# SWC_P01.net
KiCad netlist of a schematic drawn in Altium Designer
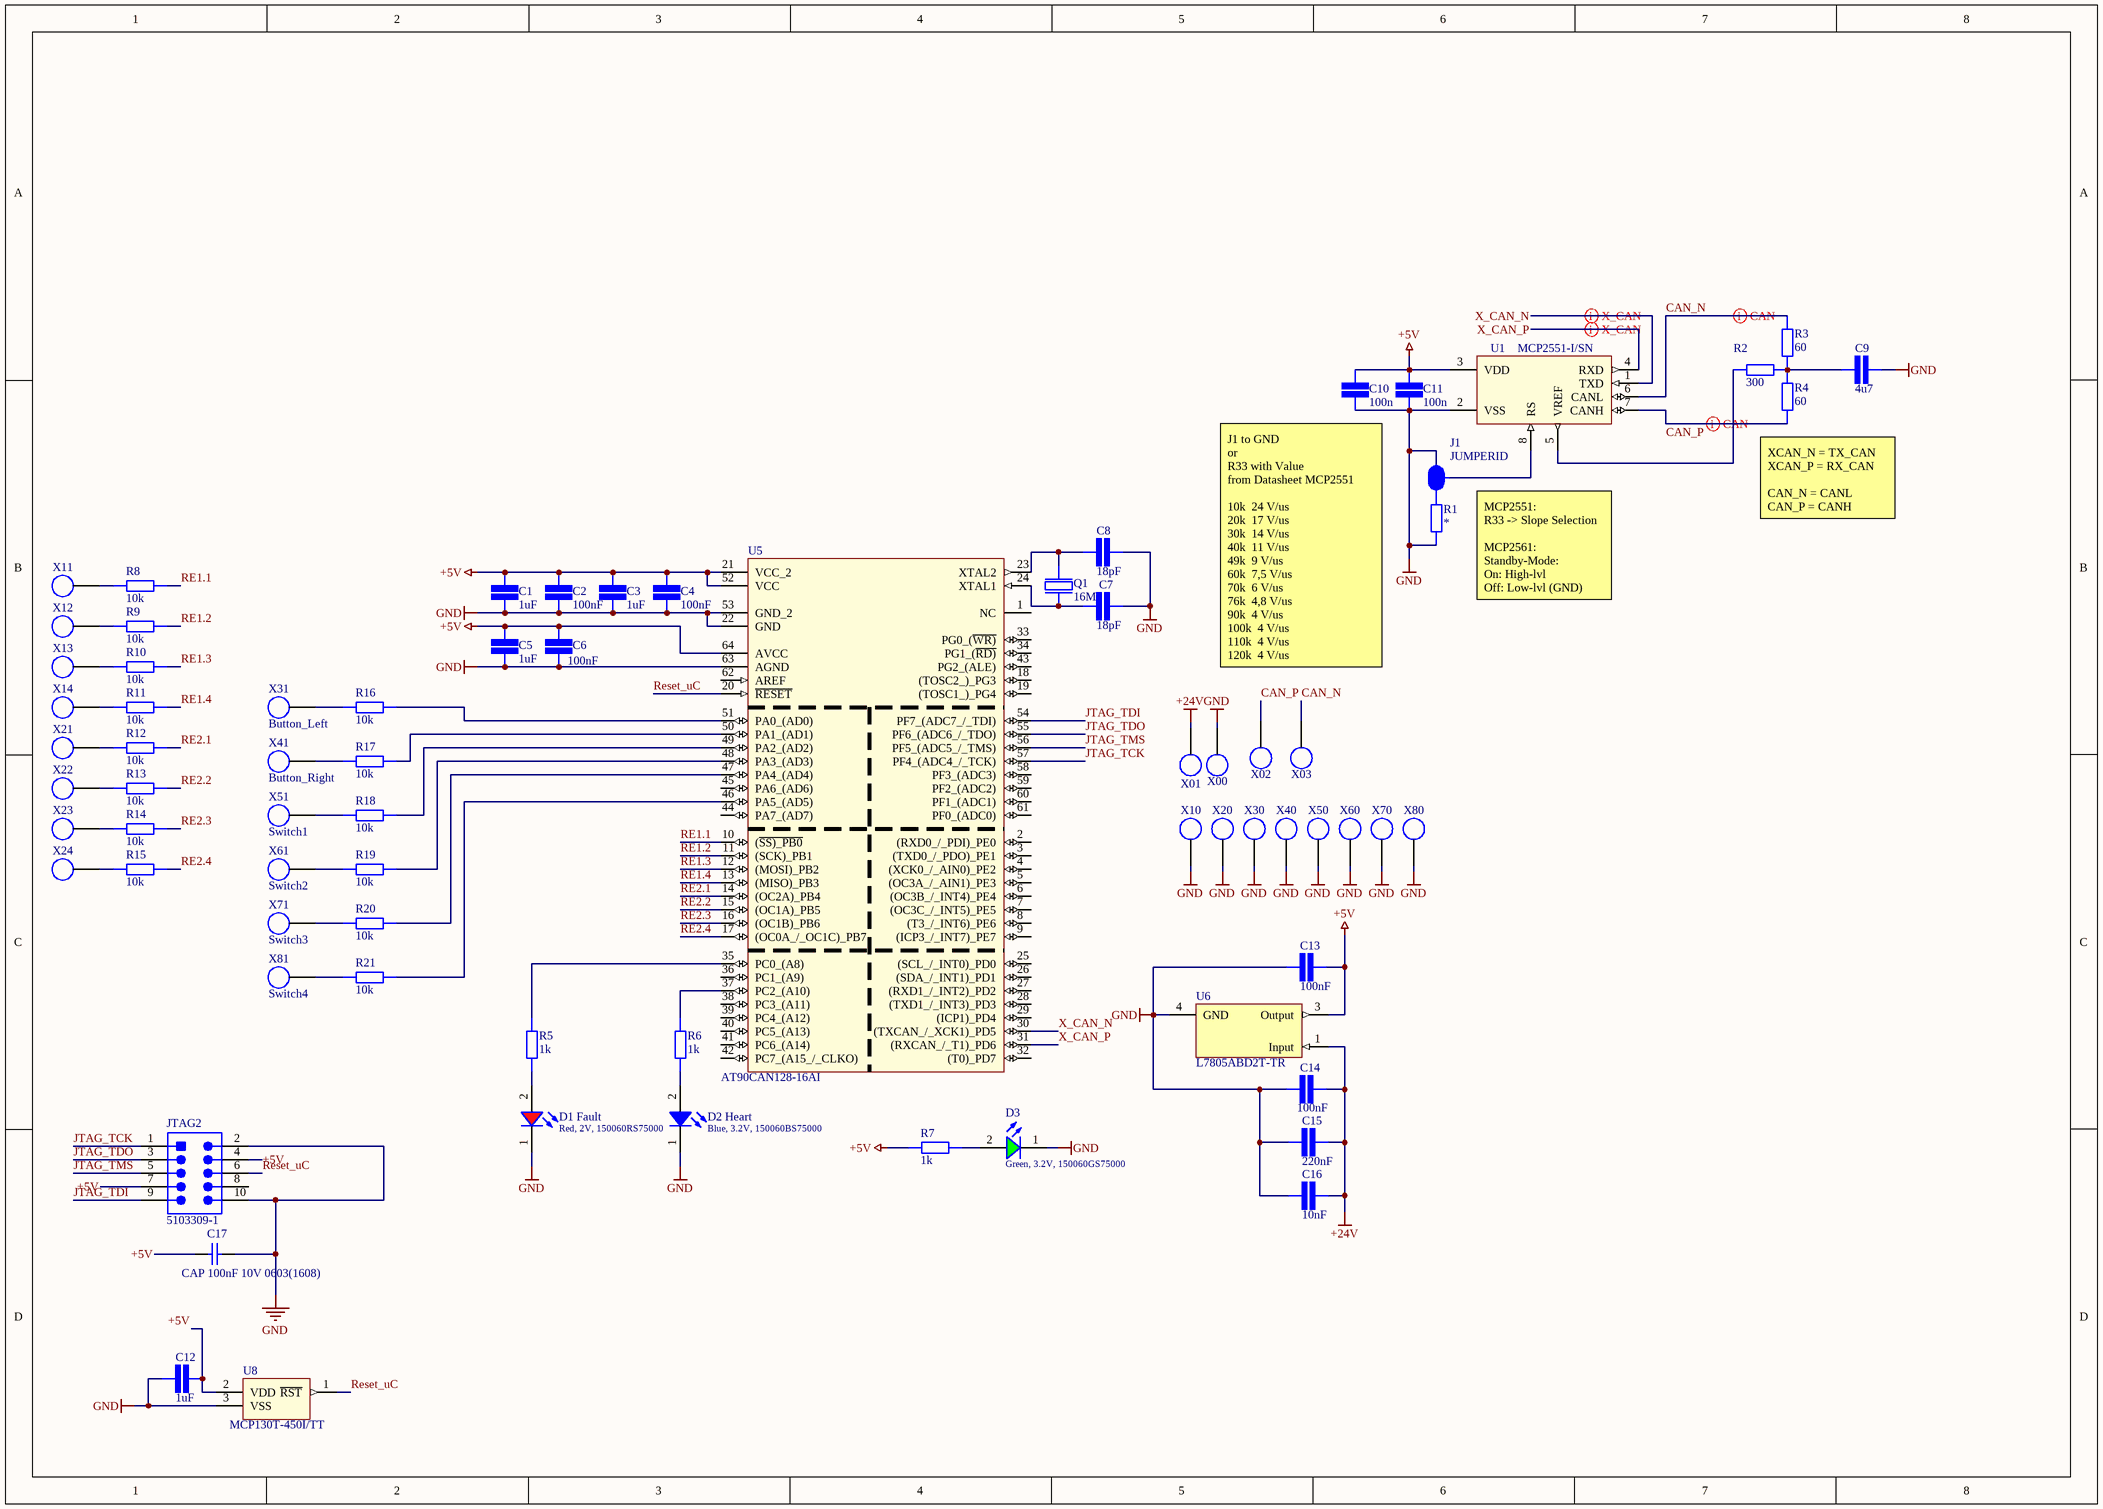
[diagram p0: SWC_P01.SchDoc]

(export (version "E")
  (design (tool "Eeschema 10.0.6"))
  (components
    (comp (ref "C1")
      (value "1uF")
      (footprint "CAP 0603/1608")
      (description "Capacitor with multiple Footprints")
      (fields (field (name "Comment") "SMD Capacitor"))
      (libsource (lib "") (part "SMD Capacitor_1"))
    )
    (comp (ref "C2")
      (value "100nF")
      (footprint "CAP 0603/1608")
      (description "Capacitor with multiple Footprints")
      (fields (field (name "Comment") "SMD Capacitor"))
      (libsource (lib "") (part "SMD Capacitor_1"))
    )
    (comp (ref "C3")
      (value "1uF")
      (footprint "CAP 0603/1608")
      (description "Capacitor with multiple Footprints")
      (fields (field (name "Comment") "SMD Capacitor"))
      (libsource (lib "") (part "SMD Capacitor_1"))
    )
    (comp (ref "C4")
      (value "100nF")
      (footprint "CAP 0603/1608")
      (description "Capacitor with multiple Footprints")
      (fields (field (name "Comment") "SMD Capacitor"))
      (libsource (lib "") (part "SMD Capacitor_1"))
    )
    (comp (ref "C5")
      (value "1uF")
      (footprint "CAP 0603/1608")
      (description "Capacitor with multiple Footprints")
      (fields (field (name "Comment") "SMD Capacitor"))
      (libsource (lib "") (part "SMD Capacitor_1"))
    )
    (comp (ref "C6")
      (value "100nF")
      (footprint "CAP 0603/1608")
      (description "Capacitor with multiple Footprints")
      (fields (field (name "Comment") "SMD Capacitor"))
      (libsource (lib "") (part "SMD Capacitor_1"))
    )
    (comp (ref "C7")
      (value "18pF")
      (footprint "CAP 0603/1608")
      (description "Capacitor with multiple Footprints")
      (fields (field (name "Comment") "SMD Capacitor"))
      (libsource (lib "Standardbauteile") (part "SMD Capacitor"))
    )
    (comp (ref "C8")
      (value "18pF")
      (footprint "CAP 0603/1608")
      (description "Capacitor with multiple Footprints")
      (fields (field (name "Comment") "SMD Capacitor"))
      (libsource (lib "Standardbauteile") (part "SMD Capacitor"))
    )
    (comp (ref "C9")
      (value "4u7")
      (footprint "CAP 0603/1608")
      (description "Capacitor with multiple Footprints")
      (fields (field (name "Comment") "SMD Capacitor"))
      (libsource (lib "") (part "SMD Capacitor_2"))
    )
    (comp (ref "C10")
      (value "100n")
      (footprint "CAP 0603/1608")
      (description "Capacitor with multiple Footprints")
      (fields (field (name "Comment") "SMD Capacitor"))
      (libsource (lib "") (part "SMD Capacitor_1"))
    )
    (comp (ref "C11")
      (value "100n")
      (footprint "CAP 0603/1608")
      (description "Capacitor with multiple Footprints")
      (fields (field (name "Comment") "SMD Capacitor"))
      (libsource (lib "") (part "SMD Capacitor_1"))
    )
    (comp (ref "C12")
      (value "1uF")
      (footprint "CAP 0603/1608")
      (description "Capacitor with multiple Footprints")
      (fields (field (name "Comment") "SMD Capacitor"))
      (libsource (lib "Standardbauteile") (part "SMD Capacitor"))
    )
    (comp (ref "C13")
      (value "100nF")
      (footprint "CAP 0603/1608")
      (description "Capacitor with multiple Footprints")
      (fields (field (name "Comment") "SMD Capacitor"))
      (libsource (lib "Standardbauteile") (part "SMD Capacitor"))
    )
    (comp (ref "C14")
      (value "100nF")
      (footprint "CAP 0603/1608")
      (description "Capacitor with multiple Footprints")
      (fields (field (name "Comment") "SMD Capacitor"))
      (libsource (lib "Standardbauteile") (part "SMD Capacitor"))
    )
    (comp (ref "C15")
      (value "220nF")
      (footprint "CAP 0603/1608")
      (description "Capacitor with multiple Footprints")
      (fields (field (name "Comment") "SMD Capacitor"))
      (libsource (lib "Standardbauteile") (part "SMD Capacitor"))
    )
    (comp (ref "C16")
      (value "10nF")
      (footprint "CAP 0603/1608")
      (description "Capacitor with multiple Footprints")
      (fields (field (name "Comment") "SMD Capacitor"))
      (libsource (lib "Standardbauteile") (part "SMD Capacitor"))
    )
    (comp (ref "C17")
      (value "CAP 100nF 10V 0603(1608)")
      (footprint "CAPC0603(1608)100_L")
      (description "CAP 100nF 10V ±5% 0603 (1608 Metric) Thickness 1mm SMD")
      (fields (field (name "TOLERANCE") "Â±5%"))
      (libsource (lib "Altium Content Vault") (part "CAP"))
    )
    (comp (ref "D1 Fault")
      (value "Red, 2V, 150060RS75000")
      (footprint "WL-SMCW_0603_H=0.7mm")
      (description "WL-SMCW SMT Mono-color Chip LED Waterclear, size 0603, Red, 2V, 140deg")
      (fields (field (name "PART NUMBER") "150060RS75000") (field (name "PUBLISHER") "Wurth Elektronik"))
      (libsource (lib "Altium_WL-SMCW (rev20a)") (part "150060RS75000"))
    )
    (comp (ref "D2 Heart")
      (value "Blue, 3.2V, 150060BS75000")
      (footprint "WL-SMCW_0603_H=0.7mm")
      (description "WL-SMCW SMT Mono-color Chip LED Waterclear, size 0603, Blue, 3.2V, 140deg")
      (fields (field (name "PART NUMBER") "150060BS75000") (field (name "PUBLISHER") "Wurth Elektronik"))
      (libsource (lib "Altium_WL-SMCW (rev20a)") (part "150060BS75000"))
    )
    (comp (ref "D3")
      (value "Green, 3.2V, 150060GS75000")
      (footprint "WL-SMCW_0603_H=0.7mm")
      (description "WL-SMCW SMT Mono-color Chip LED Waterclear, size 0603, Green, 3.2V, 140deg")
      (fields (field (name "PART NUMBER") "150060GS75000") (field (name "PUBLISHER") "Wurth Elektronik"))
      (libsource (lib "Altium_WL-SMCW (rev20a)") (part "150060GS75000"))
    )
    (comp (ref "J1")
      (value "JUMPERID")
      (footprint "SMD-JUMPER-3")
      (libsource (lib "Standardbauteile") (part "SMD Jumper 3"))
    )
    (comp (ref "JTAG2")
      (value "5103309-1")
      (footprint "TECO-5103309-1_V")
      (fields (field (name "MANUFACTURER") "TE Connectivity"))
      (libsource (lib "Altium Content Vault") (part "CN-2P-M-R10"))
    )
    (comp (ref "Q1")
      (value "16M")
      (footprint "NDK NX5032GA")
      (description "16 MHz Quartz")
      (libsource (lib "Standardbauteile") (part "16 MHz Quartz"))
    )
    (comp (ref "R1")
      (value "SMD Resistor")
      (footprint "STACKPOLE CSR0603")
      (description "Resistor with multiple footprints")
      (fields (field (name "ALTIUM_VALUE") "*"))
      (libsource (lib "Standardbauteile") (part "SMD Resistor"))
    )
    (comp (ref "R2")
      (value "300")
      (footprint "STACKPOLE CSR0603")
      (description "Resistor with multiple footprints")
      (fields (field (name "Comment") "SMD Resistor"))
      (libsource (lib "Standardbauteile") (part "SMD Resistor"))
    )
    (comp (ref "R3")
      (value "60")
      (footprint "STACKPOLE CSR0603")
      (description "Resistor with multiple footprints")
      (fields (field (name "Comment") "SMD Resistor"))
      (libsource (lib "Standardbauteile") (part "SMD Resistor"))
    )
    (comp (ref "R4")
      (value "60")
      (footprint "STACKPOLE CSR0603")
      (description "Resistor with multiple footprints")
      (fields (field (name "Comment") "SMD Resistor"))
      (libsource (lib "Standardbauteile") (part "SMD Resistor"))
    )
    (comp (ref "R5")
      (value "1k")
      (footprint "STACKPOLE CSR0603")
      (description "Resistor with multiple footprints")
      (fields (field (name "Comment") "SMD Resistor"))
      (libsource (lib "Standardbauteile") (part "SMD Resistor"))
    )
    (comp (ref "R6")
      (value "1k")
      (footprint "STACKPOLE CSR0603")
      (description "Resistor with multiple footprints")
      (fields (field (name "Comment") "SMD Resistor"))
      (libsource (lib "Standardbauteile") (part "SMD Resistor"))
    )
    (comp (ref "R7")
      (value "1k")
      (footprint "STACKPOLE CSR0603")
      (description "Resistor with multiple footprints")
      (fields (field (name "Comment") "SMD Resistor"))
      (libsource (lib "Standardbauteile") (part "SMD Resistor"))
    )
    (comp (ref "R8")
      (value "10k")
      (footprint "STACKPOLE CSR0603")
      (description "Resistor with multiple footprints")
      (fields (field (name "Comment") "SMD Resistor"))
      (libsource (lib "Standardbauteile") (part "SMD Resistor"))
    )
    (comp (ref "R9")
      (value "10k")
      (footprint "STACKPOLE CSR0603")
      (description "Resistor with multiple footprints")
      (fields (field (name "Comment") "SMD Resistor"))
      (libsource (lib "Standardbauteile") (part "SMD Resistor"))
    )
    (comp (ref "R10")
      (value "10k")
      (footprint "STACKPOLE CSR0603")
      (description "Resistor with multiple footprints")
      (fields (field (name "Comment") "SMD Resistor"))
      (libsource (lib "Standardbauteile") (part "SMD Resistor"))
    )
    (comp (ref "R11")
      (value "10k")
      (footprint "STACKPOLE CSR0603")
      (description "Resistor with multiple footprints")
      (fields (field (name "Comment") "SMD Resistor"))
      (libsource (lib "Standardbauteile") (part "SMD Resistor"))
    )
    (comp (ref "R12")
      (value "10k")
      (footprint "STACKPOLE CSR0603")
      (description "Resistor with multiple footprints")
      (fields (field (name "Comment") "SMD Resistor"))
      (libsource (lib "Standardbauteile") (part "SMD Resistor"))
    )
    (comp (ref "R13")
      (value "10k")
      (footprint "STACKPOLE CSR0603")
      (description "Resistor with multiple footprints")
      (fields (field (name "Comment") "SMD Resistor"))
      (libsource (lib "Standardbauteile") (part "SMD Resistor"))
    )
    (comp (ref "R14")
      (value "10k")
      (footprint "STACKPOLE CSR0603")
      (description "Resistor with multiple footprints")
      (fields (field (name "Comment") "SMD Resistor"))
      (libsource (lib "Standardbauteile") (part "SMD Resistor"))
    )
    (comp (ref "R15")
      (value "10k")
      (footprint "STACKPOLE CSR0603")
      (description "Resistor with multiple footprints")
      (fields (field (name "Comment") "SMD Resistor"))
      (libsource (lib "Standardbauteile") (part "SMD Resistor"))
    )
    (comp (ref "R16")
      (value "10k")
      (footprint "STACKPOLE CSR0603")
      (description "Resistor with multiple footprints")
      (fields (field (name "Comment") "SMD Resistor"))
      (libsource (lib "Standardbauteile") (part "SMD Resistor"))
    )
    (comp (ref "R17")
      (value "10k")
      (footprint "STACKPOLE CSR0603")
      (description "Resistor with multiple footprints")
      (fields (field (name "Comment") "SMD Resistor"))
      (libsource (lib "Standardbauteile") (part "SMD Resistor"))
    )
    (comp (ref "R18")
      (value "10k")
      (footprint "STACKPOLE CSR0603")
      (description "Resistor with multiple footprints")
      (fields (field (name "Comment") "SMD Resistor"))
      (libsource (lib "Standardbauteile") (part "SMD Resistor"))
    )
    (comp (ref "R19")
      (value "10k")
      (footprint "STACKPOLE CSR0603")
      (description "Resistor with multiple footprints")
      (fields (field (name "Comment") "SMD Resistor"))
      (libsource (lib "Standardbauteile") (part "SMD Resistor"))
    )
    (comp (ref "R20")
      (value "10k")
      (footprint "STACKPOLE CSR0603")
      (description "Resistor with multiple footprints")
      (fields (field (name "Comment") "SMD Resistor"))
      (libsource (lib "Standardbauteile") (part "SMD Resistor"))
    )
    (comp (ref "R21")
      (value "10k")
      (footprint "STACKPOLE CSR0603")
      (description "Resistor with multiple footprints")
      (fields (field (name "Comment") "SMD Resistor"))
      (libsource (lib "Standardbauteile") (part "SMD Resistor"))
    )
    (comp (ref "U1")
      (value "MCP2551-I/SN")
      (footprint "*SOIC127P600X175-8N")
      (description "MCP2551 Series 5.5 V 1 Mb/s Surface Mount High-Speed CAN Transceiver - SOIC-8")
      (fields (field (name "MF") "Microchip"))
      (libsource (lib "Eric") (part "MCP2551-I/SN"))
    )
    (comp (ref "U5")
      (value "AT90CAN128-16AI")
      (footprint "*QFP80P1600X1600X120-64N")
      (description "Ic Mcu 8bit 128kb Flash 64tqfp")
      (fields (field (name "MF") "Microchip"))
      (libsource (lib "Eric") (part "AT90CAN128-16AI"))
    )
    (comp (ref "U6")
      (value "L7805ABD2T-TR")
      (footprint "DPAK254P1542X460-3M")
      (description "Linear Voltage Regulators 5.0V 1.5A Positive")
      (libsource (lib "LibJulian") (part "L7805ABD2T-TR"))
    )
    (comp (ref "U8")
      (value "MCP130T-450I/TT")
      (footprint "*SOT95P237X112-3N")
      (description "System Supervisors - Power Supply Monitors with Reset Generators Open Drain Low")
      (fields (field (name "MF") "Microchip") (field (name "MP") "MCP120T-450I/TT"))
      (libsource (lib "Eric") (part "MCP130T-450I/TT"))
    )
    (comp (ref "X00")
      (value "SolderTerminal")
      (footprint "SolderTerminal")
      (libsource (lib "LibJulian") (part "SolderTerminal"))
    )
    (comp (ref "X01")
      (value "SolderTerminal")
      (footprint "SolderTerminal")
      (libsource (lib "LibJulian") (part "SolderTerminal"))
    )
    (comp (ref "X02")
      (value "SolderTerminal")
      (footprint "SolderTerminal")
      (libsource (lib "LibJulian") (part "SolderTerminal"))
    )
    (comp (ref "X03")
      (value "SolderTerminal")
      (footprint "SolderTerminal")
      (libsource (lib "LibJulian") (part "SolderTerminal"))
    )
    (comp (ref "X10")
      (value "SolderTerminal")
      (footprint "SolderTerminal")
      (libsource (lib "LibJulian") (part "SolderTerminal"))
    )
    (comp (ref "X11")
      (value "SolderTerminal")
      (footprint "SolderTerminal")
      (libsource (lib "LibJulian") (part "SolderTerminal"))
    )
    (comp (ref "X12")
      (value "SolderTerminal")
      (footprint "SolderTerminal")
      (libsource (lib "LibJulian") (part "SolderTerminal"))
    )
    (comp (ref "X13")
      (value "SolderTerminal")
      (footprint "SolderTerminal")
      (libsource (lib "LibJulian") (part "SolderTerminal"))
    )
    (comp (ref "X14")
      (value "SolderTerminal")
      (footprint "SolderTerminal")
      (libsource (lib "LibJulian") (part "SolderTerminal"))
    )
    (comp (ref "X20")
      (value "SolderTerminal")
      (footprint "SolderTerminal")
      (libsource (lib "LibJulian") (part "SolderTerminal"))
    )
    (comp (ref "X21")
      (value "SolderTerminal")
      (footprint "SolderTerminal")
      (libsource (lib "LibJulian") (part "SolderTerminal"))
    )
    (comp (ref "X22")
      (value "SolderTerminal")
      (footprint "SolderTerminal")
      (libsource (lib "LibJulian") (part "SolderTerminal"))
    )
    (comp (ref "X23")
      (value "SolderTerminal")
      (footprint "SolderTerminal")
      (libsource (lib "LibJulian") (part "SolderTerminal"))
    )
    (comp (ref "X24")
      (value "SolderTerminal")
      (footprint "SolderTerminal")
      (libsource (lib "LibJulian") (part "SolderTerminal"))
    )
    (comp (ref "X30")
      (value "SolderTerminal")
      (footprint "SolderTerminal")
      (libsource (lib "LibJulian") (part "SolderTerminal"))
    )
    (comp (ref "X31")
      (value "Button_Left")
      (footprint "SolderTerminal")
      (libsource (lib "LibJulian") (part "SolderTerminal"))
    )
    (comp (ref "X40")
      (value "SolderTerminal")
      (footprint "SolderTerminal")
      (libsource (lib "LibJulian") (part "SolderTerminal"))
    )
    (comp (ref "X41")
      (value "Button_Right")
      (footprint "SolderTerminal")
      (libsource (lib "LibJulian") (part "SolderTerminal"))
    )
    (comp (ref "X50")
      (value "SolderTerminal")
      (footprint "SolderTerminal")
      (libsource (lib "LibJulian") (part "SolderTerminal"))
    )
    (comp (ref "X51")
      (value "Switch1")
      (footprint "SolderTerminal")
      (libsource (lib "LibJulian") (part "SolderTerminal"))
    )
    (comp (ref "X60")
      (value "SolderTerminal")
      (footprint "SolderTerminal")
      (libsource (lib "LibJulian") (part "SolderTerminal"))
    )
    (comp (ref "X61")
      (value "Switch2")
      (footprint "SolderTerminal")
      (libsource (lib "LibJulian") (part "SolderTerminal"))
    )
    (comp (ref "X70")
      (value "SolderTerminal")
      (footprint "SolderTerminal")
      (libsource (lib "LibJulian") (part "SolderTerminal"))
    )
    (comp (ref "X71")
      (value "Switch3")
      (footprint "SolderTerminal")
      (libsource (lib "LibJulian") (part "SolderTerminal"))
    )
    (comp (ref "X80")
      (value "SolderTerminal")
      (footprint "SolderTerminal")
      (libsource (lib "LibJulian") (part "SolderTerminal"))
    )
    (comp (ref "X81")
      (value "Switch4")
      (footprint "SolderTerminal")
      (libsource (lib "LibJulian") (part "SolderTerminal"))
    )
  )
  (nets
    (net (code "1") (name "+5V") (class "Default")
      (node (ref "C1") (pin "2") (pinfunction "2_2") (pintype "passive"))
      (node (ref "C10") (pin "2") (pinfunction "2_2") (pintype "passive"))
      (node (ref "C11") (pin "2") (pinfunction "2_2") (pintype "passive"))
      (node (ref "C12") (pin "1") (pinfunction "1_1") (pintype "passive"))
      (node (ref "C13") (pin "1") (pinfunction "1_1") (pintype "passive"))
      (node (ref "C17") (pin "1") (pinfunction "1_1") (pintype "passive"))
      (node (ref "C2") (pin "2") (pinfunction "2_2") (pintype "passive"))
      (node (ref "C3") (pin "2") (pinfunction "2_2") (pintype "passive"))
      (node (ref "C4") (pin "2") (pinfunction "2_2") (pintype "passive"))
      (node (ref "C5") (pin "2") (pinfunction "2_2") (pintype "passive"))
      (node (ref "C6") (pin "2") (pinfunction "2_2") (pintype "passive"))
      (node (ref "JTAG2") (pin "4") (pinfunction "4_4") (pintype "passive"))
      (node (ref "JTAG2") (pin "7") (pinfunction "7_7") (pintype "passive"))
      (node (ref "R7") (pin "2") (pinfunction "2_2") (pintype "passive"))
      (node (ref "U1") (pin "3") (pinfunction "VDD_3") (pintype "power_in"))
      (node (ref "U5") (pin "21") (pinfunction "VCC_2_21") (pintype "power_in"))
      (node (ref "U5") (pin "52") (pinfunction "VCC_52") (pintype "power_in"))
      (node (ref "U5") (pin "64") (pinfunction "AVCC_64") (pintype "power_in"))
      (node (ref "U6") (pin "3") (pinfunction "Output_3") (pintype "output"))
      (node (ref "U8") (pin "2") (pinfunction "VDD_2") (pintype "power_in"))
    )
    (net (code "2") (name "+24V") (class "Default")
      (node (ref "C14") (pin "1") (pinfunction "1_1") (pintype "passive"))
      (node (ref "C15") (pin "1") (pinfunction "1_1") (pintype "passive"))
      (node (ref "C16") (pin "1") (pinfunction "1_1") (pintype "passive"))
      (node (ref "U6") (pin "1") (pinfunction "Input_1") (pintype "input"))
      (node (ref "X01") (pin "1") (pinfunction "Terminal_1") (pintype "passive"))
    )
    (net (code "3") (name "/CAN_N") (class "Default")
      (node (ref "R3") (pin "1") (pinfunction "1_1") (pintype "passive"))
      (node (ref "U1") (pin "6") (pinfunction "CANL_6") (pintype "bidirectional"))
      (node (ref "X03") (pin "1") (pinfunction "Terminal_1") (pintype "passive"))
    )
    (net (code "4") (name "/CAN_P") (class "Default")
      (node (ref "R4") (pin "2") (pinfunction "2_2") (pintype "passive"))
      (node (ref "U1") (pin "7") (pinfunction "CANH_7") (pintype "bidirectional"))
      (node (ref "X02") (pin "1") (pinfunction "Terminal_1") (pintype "passive"))
    )
    (net (code "5") (name "/JTAG_TCK") (class "Default")
      (node (ref "JTAG2") (pin "1") (pinfunction "1_1") (pintype "passive"))
      (node (ref "U5") (pin "57") (pinfunction "PF4_(ADC4_/_TCK)_57") (pintype "bidirectional"))
    )
    (net (code "6") (name "/JTAG_TDI") (class "Default")
      (node (ref "JTAG2") (pin "9") (pinfunction "9_9") (pintype "passive"))
      (node (ref "U5") (pin "54") (pinfunction "PF7_(ADC7_/_TDI)_54") (pintype "bidirectional"))
    )
    (net (code "7") (name "/JTAG_TDO") (class "Default")
      (node (ref "JTAG2") (pin "3") (pinfunction "3_3") (pintype "passive"))
      (node (ref "U5") (pin "55") (pinfunction "PF6_(ADC6_/_TDO)_55") (pintype "bidirectional"))
    )
    (net (code "8") (name "/JTAG_TMS") (class "Default")
      (node (ref "JTAG2") (pin "5") (pinfunction "5_5") (pintype "passive"))
      (node (ref "U5") (pin "56") (pinfunction "PF5_(ADC5_/_TMS)_56") (pintype "bidirectional"))
    )
    (net (code "9") (name "/RE1.1") (class "Default")
      (node (ref "R8") (pin "1") (pinfunction "1_1") (pintype "passive"))
      (node (ref "U5") (pin "10") (pinfunction "(~{SS)_PB0}_10") (pintype "bidirectional"))
    )
    (net (code "10") (name "/RE1.2") (class "Default")
      (node (ref "R9") (pin "1") (pinfunction "1_1") (pintype "passive"))
      (node (ref "U5") (pin "11") (pinfunction "(SCK)_PB1_11") (pintype "bidirectional"))
    )
    (net (code "11") (name "/RE1.3") (class "Default")
      (node (ref "R10") (pin "1") (pinfunction "1_1") (pintype "passive"))
      (node (ref "U5") (pin "12") (pinfunction "(MOSI)_PB2_12") (pintype "bidirectional"))
    )
    (net (code "12") (name "/RE1.4") (class "Default")
      (node (ref "R11") (pin "1") (pinfunction "1_1") (pintype "passive"))
      (node (ref "U5") (pin "13") (pinfunction "(MISO)_PB3_13") (pintype "bidirectional"))
    )
    (net (code "13") (name "/RE2.1") (class "Default")
      (node (ref "R12") (pin "1") (pinfunction "1_1") (pintype "passive"))
      (node (ref "U5") (pin "14") (pinfunction "(OC2A)_PB4_14") (pintype "bidirectional"))
    )
    (net (code "14") (name "/RE2.2") (class "Default")
      (node (ref "R13") (pin "1") (pinfunction "1_1") (pintype "passive"))
      (node (ref "U5") (pin "15") (pinfunction "(OC1A)_PB5_15") (pintype "bidirectional"))
    )
    (net (code "15") (name "/RE2.3") (class "Default")
      (node (ref "R14") (pin "1") (pinfunction "1_1") (pintype "passive"))
      (node (ref "U5") (pin "16") (pinfunction "(OC1B)_PB6_16") (pintype "bidirectional"))
    )
    (net (code "16") (name "/RE2.4") (class "Default")
      (node (ref "R15") (pin "1") (pinfunction "1_1") (pintype "passive"))
      (node (ref "U5") (pin "17") (pinfunction "(OC0A_/_OC1C)_PB7_17") (pintype "bidirectional"))
    )
    (net (code "17") (name "/Reset_uC") (class "Default")
      (node (ref "JTAG2") (pin "6") (pinfunction "6_6") (pintype "passive"))
      (node (ref "U5") (pin "20") (pinfunction "~{RESET}_20") (pintype "input"))
      (node (ref "U8") (pin "1") (pinfunction "~{RST}_1") (pintype "output"))
    )
    (net (code "18") (name "/X_CAN_N") (class "Default")
      (node (ref "U1") (pin "1") (pinfunction "TXD_1") (pintype "input"))
      (node (ref "U5") (pin "30") (pinfunction "(TXCAN_/_XCK1)_PD5_30") (pintype "bidirectional"))
    )
    (net (code "19") (name "/X_CAN_P") (class "Default")
      (node (ref "U1") (pin "4") (pinfunction "RXD_4") (pintype "output"))
      (node (ref "U5") (pin "31") (pinfunction "(RXCAN_/_T1)_PD6_31") (pintype "bidirectional"))
    )
    (net (code "20") (name "GND") (class "Default")
      (node (ref "C1") (pin "1") (pinfunction "1_1") (pintype "passive"))
      (node (ref "C10") (pin "1") (pinfunction "1_1") (pintype "passive"))
      (node (ref "C11") (pin "1") (pinfunction "1_1") (pintype "passive"))
      (node (ref "C12") (pin "2") (pinfunction "2_2") (pintype "passive"))
      (node (ref "C13") (pin "2") (pinfunction "2_2") (pintype "passive"))
      (node (ref "C14") (pin "2") (pinfunction "2_2") (pintype "passive"))
      (node (ref "C15") (pin "2") (pinfunction "2_2") (pintype "passive"))
      (node (ref "C16") (pin "2") (pinfunction "2_2") (pintype "passive"))
      (node (ref "C17") (pin "2") (pinfunction "2_2") (pintype "passive"))
      (node (ref "C2") (pin "1") (pinfunction "1_1") (pintype "passive"))
      (node (ref "C3") (pin "1") (pinfunction "1_1") (pintype "passive"))
      (node (ref "C4") (pin "1") (pinfunction "1_1") (pintype "passive"))
      (node (ref "C5") (pin "1") (pinfunction "1_1") (pintype "passive"))
      (node (ref "C6") (pin "1") (pinfunction "1_1") (pintype "passive"))
      (node (ref "C7") (pin "1") (pinfunction "1_1") (pintype "passive"))
      (node (ref "C8") (pin "1") (pinfunction "1_1") (pintype "passive"))
      (node (ref "C9") (pin "2") (pinfunction "2_2") (pintype "passive"))
      (node (ref "D1 Fault") (pin "1") (pinfunction "K_1") (pintype "passive"))
      (node (ref "D2 Heart") (pin "1") (pinfunction "K_1") (pintype "passive"))
      (node (ref "D3") (pin "1") (pinfunction "K_1") (pintype "passive"))
      (node (ref "J1") (pin "1") (pinfunction "1_1") (pintype "passive"))
      (node (ref "JTAG2") (pin "10") (pinfunction "10_10") (pintype "passive"))
      (node (ref "JTAG2") (pin "2") (pinfunction "2_2") (pintype "passive"))
      (node (ref "R1") (pin "1") (pinfunction "1_1") (pintype "passive"))
      (node (ref "U1") (pin "2") (pinfunction "VSS_2") (pintype "passive"))
      (node (ref "U5") (pin "22") (pinfunction "GND_22") (pintype "passive"))
      (node (ref "U5") (pin "53") (pinfunction "GND_2_53") (pintype "passive"))
      (node (ref "U5") (pin "63") (pinfunction "AGND_63") (pintype "passive"))
      (node (ref "U6") (pin "4") (pinfunction "GND_4") (pintype "passive"))
      (node (ref "U8") (pin "3") (pinfunction "VSS_3") (pintype "power_in"))
      (node (ref "X00") (pin "1") (pinfunction "Terminal_1") (pintype "passive"))
      (node (ref "X10") (pin "1") (pinfunction "Terminal_1") (pintype "passive"))
      (node (ref "X20") (pin "1") (pinfunction "Terminal_1") (pintype "passive"))
      (node (ref "X30") (pin "1") (pinfunction "Terminal_1") (pintype "passive"))
      (node (ref "X40") (pin "1") (pinfunction "Terminal_1") (pintype "passive"))
      (node (ref "X50") (pin "1") (pinfunction "Terminal_1") (pintype "passive"))
      (node (ref "X60") (pin "1") (pinfunction "Terminal_1") (pintype "passive"))
      (node (ref "X70") (pin "1") (pinfunction "Terminal_1") (pintype "passive"))
      (node (ref "X80") (pin "1") (pinfunction "Terminal_1") (pintype "passive"))
    )
    (net (code "21") (name "Net-(C9-Pad1)") (class "Default")
      (node (ref "C9") (pin "1") (pinfunction "1_1") (pintype "passive"))
      (node (ref "R2") (pin "2") (pinfunction "2_2") (pintype "passive"))
      (node (ref "R3") (pin "2") (pinfunction "2_2") (pintype "passive"))
      (node (ref "R4") (pin "1") (pinfunction "1_1") (pintype "passive"))
    )
    (net (code "22") (name "Net-(D1 Fault-A)") (class "Default")
      (node (ref "D1 Fault") (pin "2") (pinfunction "A_2") (pintype "passive"))
      (node (ref "R5") (pin "2") (pinfunction "2_2") (pintype "passive"))
    )
    (net (code "23") (name "Net-(D2 Heart-A)") (class "Default")
      (node (ref "D2 Heart") (pin "2") (pinfunction "A_2") (pintype "passive"))
      (node (ref "R6") (pin "2") (pinfunction "2_2") (pintype "passive"))
    )
    (net (code "24") (name "Net-(D3-A)") (class "Default")
      (node (ref "D3") (pin "2") (pinfunction "A_2") (pintype "passive"))
      (node (ref "R7") (pin "1") (pinfunction "1_1") (pintype "passive"))
    )
    (net (code "25") (name "Net-(J1-Pad3)") (class "Default")
      (node (ref "J1") (pin "3") (pinfunction "3_3") (pintype "passive"))
      (node (ref "R1") (pin "2") (pinfunction "2_2") (pintype "passive"))
    )
    (net (code "26") (name "Net-(U1-RS)") (class "Default")
      (node (ref "J1") (pin "2") (pinfunction "2_2") (pintype "passive"))
      (node (ref "U1") (pin "8") (pinfunction "RS_8") (pintype "input"))
    )
    (net (code "27") (name "Net-(U1-VREF)") (class "Default")
      (node (ref "R2") (pin "1") (pinfunction "1_1") (pintype "passive"))
      (node (ref "U1") (pin "5") (pinfunction "VREF_5") (pintype "output"))
    )
    (net (code "28") (name "Net-(U5-PA0_(AD0))") (class "Default")
      (node (ref "R16") (pin "2") (pinfunction "2_2") (pintype "passive"))
      (node (ref "U5") (pin "51") (pinfunction "PA0_(AD0)_51") (pintype "bidirectional"))
    )
    (net (code "29") (name "Net-(U5-PA1_(AD1))") (class "Default")
      (node (ref "R17") (pin "2") (pinfunction "2_2") (pintype "passive"))
      (node (ref "U5") (pin "50") (pinfunction "PA1_(AD1)_50") (pintype "bidirectional"))
    )
    (net (code "30") (name "Net-(U5-PA2_(AD2))") (class "Default")
      (node (ref "R18") (pin "2") (pinfunction "2_2") (pintype "passive"))
      (node (ref "U5") (pin "49") (pinfunction "PA2_(AD2)_49") (pintype "bidirectional"))
    )
    (net (code "31") (name "Net-(U5-PA3_(AD3))") (class "Default")
      (node (ref "R19") (pin "2") (pinfunction "2_2") (pintype "passive"))
      (node (ref "U5") (pin "48") (pinfunction "PA3_(AD3)_48") (pintype "bidirectional"))
    )
    (net (code "32") (name "Net-(U5-PA4_(AD4))") (class "Default")
      (node (ref "R20") (pin "2") (pinfunction "2_2") (pintype "passive"))
      (node (ref "U5") (pin "47") (pinfunction "PA4_(AD4)_47") (pintype "bidirectional"))
    )
    (net (code "33") (name "Net-(U5-PA5_(AD5))") (class "Default")
      (node (ref "R21") (pin "2") (pinfunction "2_2") (pintype "passive"))
      (node (ref "U5") (pin "46") (pinfunction "PA5_(AD5)_46") (pintype "bidirectional"))
    )
    (net (code "34") (name "Net-(U5-PC0_(A8))") (class "Default")
      (node (ref "R5") (pin "1") (pinfunction "1_1") (pintype "passive"))
      (node (ref "U5") (pin "35") (pinfunction "PC0_(A8)_35") (pintype "bidirectional"))
    )
    (net (code "35") (name "Net-(U5-PC2_(A10))") (class "Default")
      (node (ref "R6") (pin "1") (pinfunction "1_1") (pintype "passive"))
      (node (ref "U5") (pin "37") (pinfunction "PC2_(A10)_37") (pintype "bidirectional"))
    )
    (net (code "36") (name "Net-(U5-XTAL1)") (class "Default")
      (node (ref "C7") (pin "2") (pinfunction "2_2") (pintype "passive"))
      (node (ref "Q1") (pin "1") (pinfunction "1_1") (pintype "passive"))
      (node (ref "U5") (pin "24") (pinfunction "XTAL1_24") (pintype "input"))
    )
    (net (code "37") (name "Net-(U5-XTAL2)") (class "Default")
      (node (ref "C8") (pin "2") (pinfunction "2_2") (pintype "passive"))
      (node (ref "Q1") (pin "2") (pinfunction "2_2") (pintype "passive"))
      (node (ref "U5") (pin "23") (pinfunction "XTAL2_23") (pintype "output"))
    )
    (net (code "38") (name "Net-(X11-Terminal)") (class "Default")
      (node (ref "R8") (pin "2") (pinfunction "2_2") (pintype "passive"))
      (node (ref "X11") (pin "1") (pinfunction "Terminal_1") (pintype "passive"))
    )
    (net (code "39") (name "Net-(X12-Terminal)") (class "Default")
      (node (ref "R9") (pin "2") (pinfunction "2_2") (pintype "passive"))
      (node (ref "X12") (pin "1") (pinfunction "Terminal_1") (pintype "passive"))
    )
    (net (code "40") (name "Net-(X13-Terminal)") (class "Default")
      (node (ref "R10") (pin "2") (pinfunction "2_2") (pintype "passive"))
      (node (ref "X13") (pin "1") (pinfunction "Terminal_1") (pintype "passive"))
    )
    (net (code "41") (name "Net-(X14-Terminal)") (class "Default")
      (node (ref "R11") (pin "2") (pinfunction "2_2") (pintype "passive"))
      (node (ref "X14") (pin "1") (pinfunction "Terminal_1") (pintype "passive"))
    )
    (net (code "42") (name "Net-(X21-Terminal)") (class "Default")
      (node (ref "R12") (pin "2") (pinfunction "2_2") (pintype "passive"))
      (node (ref "X21") (pin "1") (pinfunction "Terminal_1") (pintype "passive"))
    )
    (net (code "43") (name "Net-(X22-Terminal)") (class "Default")
      (node (ref "R13") (pin "2") (pinfunction "2_2") (pintype "passive"))
      (node (ref "X22") (pin "1") (pinfunction "Terminal_1") (pintype "passive"))
    )
    (net (code "44") (name "Net-(X23-Terminal)") (class "Default")
      (node (ref "R14") (pin "2") (pinfunction "2_2") (pintype "passive"))
      (node (ref "X23") (pin "1") (pinfunction "Terminal_1") (pintype "passive"))
    )
    (net (code "45") (name "Net-(X24-Terminal)") (class "Default")
      (node (ref "R15") (pin "2") (pinfunction "2_2") (pintype "passive"))
      (node (ref "X24") (pin "1") (pinfunction "Terminal_1") (pintype "passive"))
    )
    (net (code "46") (name "Net-(X31-Terminal)") (class "Default")
      (node (ref "R16") (pin "1") (pinfunction "1_1") (pintype "passive"))
      (node (ref "X31") (pin "1") (pinfunction "Terminal_1") (pintype "passive"))
    )
    (net (code "47") (name "Net-(X41-Terminal)") (class "Default")
      (node (ref "R17") (pin "1") (pinfunction "1_1") (pintype "passive"))
      (node (ref "X41") (pin "1") (pinfunction "Terminal_1") (pintype "passive"))
    )
    (net (code "48") (name "Net-(X51-Terminal)") (class "Default")
      (node (ref "R18") (pin "1") (pinfunction "1_1") (pintype "passive"))
      (node (ref "X51") (pin "1") (pinfunction "Terminal_1") (pintype "passive"))
    )
    (net (code "49") (name "Net-(X61-Terminal)") (class "Default")
      (node (ref "R19") (pin "1") (pinfunction "1_1") (pintype "passive"))
      (node (ref "X61") (pin "1") (pinfunction "Terminal_1") (pintype "passive"))
    )
    (net (code "50") (name "Net-(X71-Terminal)") (class "Default")
      (node (ref "R20") (pin "1") (pinfunction "1_1") (pintype "passive"))
      (node (ref "X71") (pin "1") (pinfunction "Terminal_1") (pintype "passive"))
    )
    (net (code "51") (name "Net-(X81-Terminal)") (class "Default")
      (node (ref "R21") (pin "1") (pinfunction "1_1") (pintype "passive"))
      (node (ref "X81") (pin "1") (pinfunction "Terminal_1") (pintype "passive"))
    )
    (net (code "52") (name "unconnected-(JTAG2-Pad8)") (class "Default")
      (node (ref "JTAG2") (pin "8") (pinfunction "8_8") (pintype "passive"))
    )
    (net (code "53") (name "unconnected-(U5-(ICP1)_PD4-Pad29)") (class "Default")
      (node (ref "U5") (pin "29") (pinfunction "(ICP1)_PD4_29") (pintype "bidirectional"))
    )
    (net (code "54") (name "unconnected-(U5-(ICP3_{slash}_INT7)_PE7-Pad9)") (class "Default")
      (node (ref "U5") (pin "9") (pinfunction "(ICP3_/_INT7)_PE7_9") (pintype "bidirectional"))
    )
    (net (code "55") (name "unconnected-(U5-(OC3A_{slash}_AIN1)_PE3-Pad5)") (class "Default")
      (node (ref "U5") (pin "5") (pinfunction "(OC3A_/_AIN1)_PE3_5") (pintype "bidirectional"))
    )
    (net (code "56") (name "unconnected-(U5-(OC3B_{slash}_INT4)_PE4-Pad6)") (class "Default")
      (node (ref "U5") (pin "6") (pinfunction "(OC3B_/_INT4)_PE4_6") (pintype "bidirectional"))
    )
    (net (code "57") (name "unconnected-(U5-(OC3C_{slash}_INT5)_PE5-Pad7)") (class "Default")
      (node (ref "U5") (pin "7") (pinfunction "(OC3C_/_INT5)_PE5_7") (pintype "bidirectional"))
    )
    (net (code "58") (name "unconnected-(U5-(RXD0_{slash}_PDI)_PE0-Pad2)") (class "Default")
      (node (ref "U5") (pin "2") (pinfunction "(RXD0_/_PDI)_PE0_2") (pintype "bidirectional"))
    )
    (net (code "59") (name "unconnected-(U5-(RXD1_{slash}_INT2)_PD2-Pad27)") (class "Default")
      (node (ref "U5") (pin "27") (pinfunction "(RXD1_/_INT2)_PD2_27") (pintype "bidirectional"))
    )
    (net (code "60") (name "unconnected-(U5-(SCL_{slash}_INT0)_PD0-Pad25)") (class "Default")
      (node (ref "U5") (pin "25") (pinfunction "(SCL_/_INT0)_PD0_25") (pintype "bidirectional"))
    )
    (net (code "61") (name "unconnected-(U5-(SDA_{slash}_INT1)_PD1-Pad26)") (class "Default")
      (node (ref "U5") (pin "26") (pinfunction "(SDA_/_INT1)_PD1_26") (pintype "bidirectional"))
    )
    (net (code "62") (name "unconnected-(U5-(T0)_PD7-Pad32)") (class "Default")
      (node (ref "U5") (pin "32") (pinfunction "(T0)_PD7_32") (pintype "bidirectional"))
    )
    (net (code "63") (name "unconnected-(U5-(T3_{slash}_INT6)_PE6-Pad8)") (class "Default")
      (node (ref "U5") (pin "8") (pinfunction "(T3_/_INT6)_PE6_8") (pintype "bidirectional"))
    )
    (net (code "64") (name "unconnected-(U5-(TOSC1_)_PG4-Pad19)") (class "Default")
      (node (ref "U5") (pin "19") (pinfunction "(TOSC1_)_PG4_19") (pintype "bidirectional"))
    )
    (net (code "65") (name "unconnected-(U5-(TOSC2_)_PG3-Pad18)") (class "Default")
      (node (ref "U5") (pin "18") (pinfunction "(TOSC2_)_PG3_18") (pintype "bidirectional"))
    )
    (net (code "66") (name "unconnected-(U5-(TXD0_{slash}_PDO)_PE1-Pad3)") (class "Default")
      (node (ref "U5") (pin "3") (pinfunction "(TXD0_/_PDO)_PE1_3") (pintype "bidirectional"))
    )
    (net (code "67") (name "unconnected-(U5-(TXD1_{slash}_INT3)_PD3-Pad28)") (class "Default")
      (node (ref "U5") (pin "28") (pinfunction "(TXD1_/_INT3)_PD3_28") (pintype "bidirectional"))
    )
    (net (code "68") (name "unconnected-(U5-(XCK0_{slash}_AIN0)_PE2-Pad4)") (class "Default")
      (node (ref "U5") (pin "4") (pinfunction "(XCK0_/_AIN0)_PE2_4") (pintype "bidirectional"))
    )
    (net (code "69") (name "unconnected-(U5-AREF-Pad62)") (class "Default")
      (node (ref "U5") (pin "62") (pinfunction "AREF_62") (pintype "input"))
    )
    (net (code "70") (name "unconnected-(U5-NC-Pad1)") (class "Default")
      (node (ref "U5") (pin "1") (pinfunction "NC_1") (pintype "passive"))
    )
    (net (code "71") (name "unconnected-(U5-PA6_(AD6)-Pad45)") (class "Default")
      (node (ref "U5") (pin "45") (pinfunction "PA6_(AD6)_45") (pintype "bidirectional"))
    )
    (net (code "72") (name "unconnected-(U5-PA7_(AD7)-Pad44)") (class "Default")
      (node (ref "U5") (pin "44") (pinfunction "PA7_(AD7)_44") (pintype "bidirectional"))
    )
    (net (code "73") (name "unconnected-(U5-PC1_(A9)-Pad36)") (class "Default")
      (node (ref "U5") (pin "36") (pinfunction "PC1_(A9)_36") (pintype "bidirectional"))
    )
    (net (code "74") (name "unconnected-(U5-PC3_(A11)-Pad38)") (class "Default")
      (node (ref "U5") (pin "38") (pinfunction "PC3_(A11)_38") (pintype "bidirectional"))
    )
    (net (code "75") (name "unconnected-(U5-PC4_(A12)-Pad39)") (class "Default")
      (node (ref "U5") (pin "39") (pinfunction "PC4_(A12)_39") (pintype "bidirectional"))
    )
    (net (code "76") (name "unconnected-(U5-PC5_(A13)-Pad40)") (class "Default")
      (node (ref "U5") (pin "40") (pinfunction "PC5_(A13)_40") (pintype "bidirectional"))
    )
    (net (code "77") (name "unconnected-(U5-PC6_(A14)-Pad41)") (class "Default")
      (node (ref "U5") (pin "41") (pinfunction "PC6_(A14)_41") (pintype "bidirectional"))
    )
    (net (code "78") (name "unconnected-(U5-PC7_(A15_{slash}_CLKO)-Pad42)") (class "Default")
      (node (ref "U5") (pin "42") (pinfunction "PC7_(A15_/_CLKO)_42") (pintype "bidirectional"))
    )
    (net (code "79") (name "unconnected-(U5-PF0_(ADC0)-Pad61)") (class "Default")
      (node (ref "U5") (pin "61") (pinfunction "PF0_(ADC0)_61") (pintype "bidirectional"))
    )
    (net (code "80") (name "unconnected-(U5-PF1_(ADC1)-Pad60)") (class "Default")
      (node (ref "U5") (pin "60") (pinfunction "PF1_(ADC1)_60") (pintype "bidirectional"))
    )
    (net (code "81") (name "unconnected-(U5-PF2_(ADC2)-Pad59)") (class "Default")
      (node (ref "U5") (pin "59") (pinfunction "PF2_(ADC2)_59") (pintype "bidirectional"))
    )
    (net (code "82") (name "unconnected-(U5-PF3_(ADC3)-Pad58)") (class "Default")
      (node (ref "U5") (pin "58") (pinfunction "PF3_(ADC3)_58") (pintype "bidirectional"))
    )
    (net (code "83") (name "unconnected-(U5-PG0_(~{WR)}-Pad33)") (class "Default")
      (node (ref "U5") (pin "33") (pinfunction "PG0_(~{WR)}_33") (pintype "bidirectional"))
    )
    (net (code "84") (name "unconnected-(U5-PG1_(~{RD)}-Pad34)") (class "Default")
      (node (ref "U5") (pin "34") (pinfunction "PG1_(~{RD)}_34") (pintype "bidirectional"))
    )
    (net (code "85") (name "unconnected-(U5-PG2_(ALE)-Pad43)") (class "Default")
      (node (ref "U5") (pin "43") (pinfunction "PG2_(ALE)_43") (pintype "bidirectional"))
    )
  )
)
